# Main.net
KiCad netlist of a schematic drawn in Altium Designer
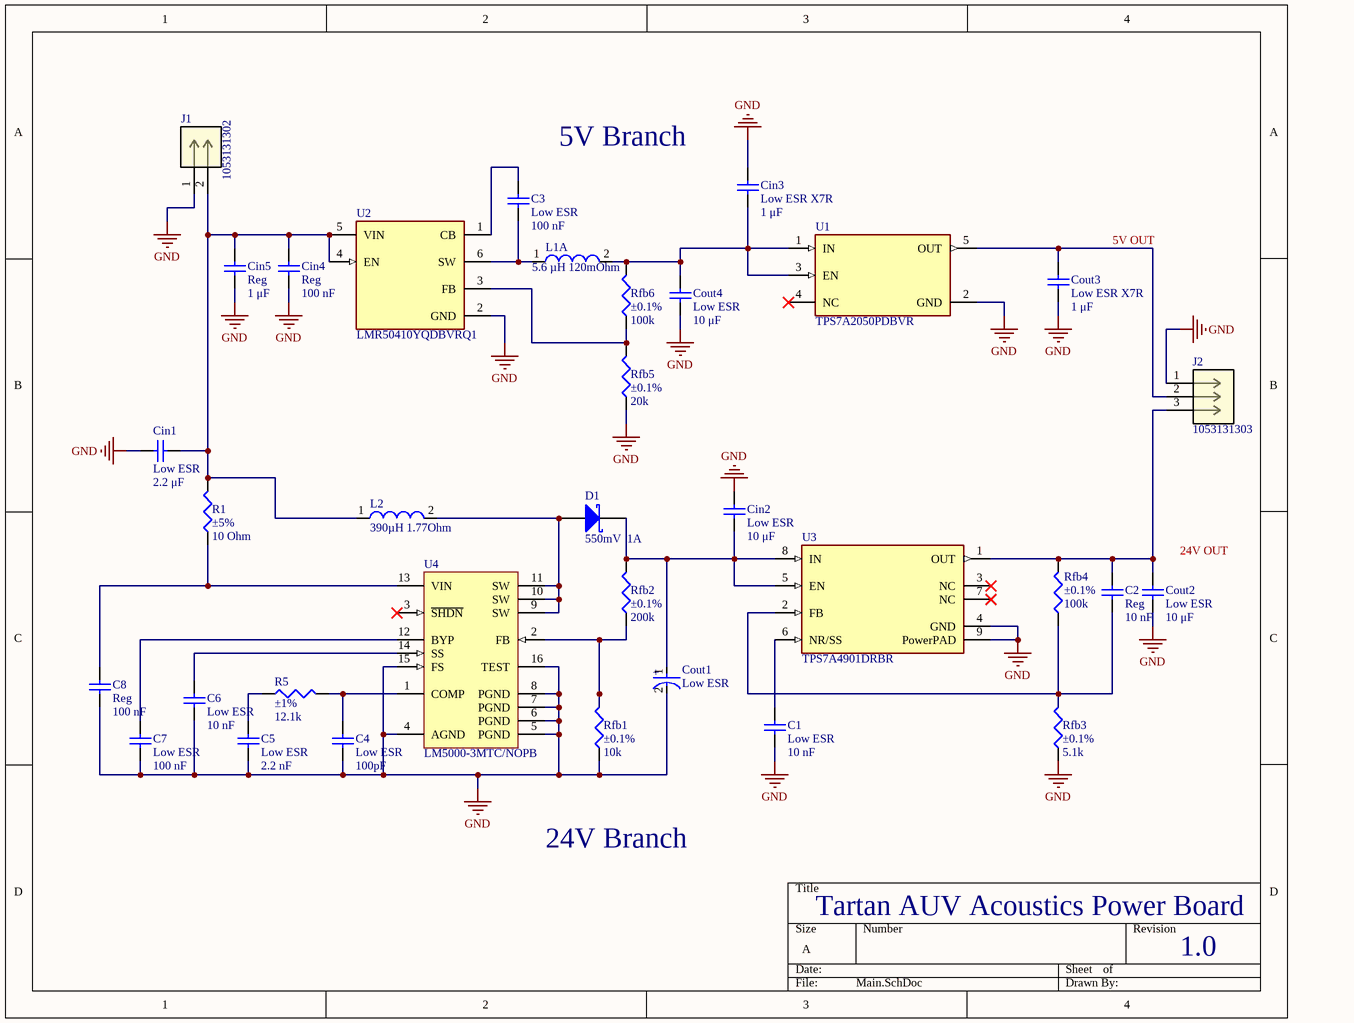
[diagram p0: Main.SchDoc]

(export (version "E")
  (design (tool "Eeschema 10.0.6"))
  (components
    (comp (ref "C1")
      (value "Low ESR")
      (footprint "C0805")
      (description "Capacitor")
      (fields (field (name "ALTIUM_VALUE") "10 nF") (field (name "PUBLISHER") "Altium Limited"))
      (libsource (lib "Miscellaneous Devices") (part "Cap"))
    )
    (comp (ref "C2")
      (value "Reg")
      (footprint "C0805")
      (description "Capacitor")
      (fields (field (name "ALTIUM_VALUE") "10 nF") (field (name "PUBLISHER") "Altium Limited"))
      (libsource (lib "Miscellaneous Devices") (part "Cap"))
    )
    (comp (ref "C3")
      (value "Low ESR")
      (footprint "C0805")
      (description "Capacitor")
      (fields (field (name "ALTIUM_VALUE") "100 nF") (field (name "PUBLISHER") "Altium Limited"))
      (libsource (lib "Miscellaneous Devices") (part "Cap"))
    )
    (comp (ref "C4")
      (value "Low ESR")
      (footprint "C0805")
      (description "Capacitor")
      (fields (field (name "ALTIUM_VALUE") "100pF") (field (name "PUBLISHER") "Altium Limited"))
      (libsource (lib "Miscellaneous Devices") (part "Cap"))
    )
    (comp (ref "C5")
      (value "Low ESR")
      (footprint "C0805")
      (description "Capacitor")
      (fields (field (name "ALTIUM_VALUE") "2.2 nF") (field (name "PUBLISHER") "Altium Limited"))
      (libsource (lib "Miscellaneous Devices") (part "Cap"))
    )
    (comp (ref "C6")
      (value "Low ESR")
      (footprint "C0805")
      (description "Capacitor")
      (fields (field (name "ALTIUM_VALUE") "10 nF") (field (name "PUBLISHER") "Altium Limited"))
      (libsource (lib "Miscellaneous Devices") (part "Cap"))
    )
    (comp (ref "C7")
      (value "Low ESR")
      (footprint "C0805")
      (description "Capacitor")
      (fields (field (name "ALTIUM_VALUE") "100 nF") (field (name "PUBLISHER") "Altium Limited"))
      (libsource (lib "Miscellaneous Devices") (part "Cap"))
    )
    (comp (ref "C8")
      (value "Reg")
      (footprint "C0805")
      (description "Capacitor")
      (fields (field (name "ALTIUM_VALUE") "100 nF") (field (name "PUBLISHER") "Altium Limited"))
      (libsource (lib "Miscellaneous Devices") (part "Cap"))
    )
    (comp (ref "Cin1")
      (value "Low ESR")
      (footprint "C0805")
      (description "Capacitor")
      (fields (field (name "ALTIUM_VALUE") "2.2 μF") (field (name "PUBLISHER") "Altium Limited"))
      (libsource (lib "Miscellaneous Devices") (part "Cap"))
    )
    (comp (ref "Cin2")
      (value "Low ESR")
      (footprint "C1210")
      (description "Capacitor")
      (fields (field (name "ALTIUM_VALUE") "10 μF") (field (name "PUBLISHER") "Altium Limited"))
      (libsource (lib "Miscellaneous Devices") (part "Cap"))
    )
    (comp (ref "Cin3")
      (value "Low ESR X7R")
      (footprint "C0805")
      (description "Capacitor")
      (fields (field (name "ALTIUM_VALUE") "1 μF") (field (name "PUBLISHER") "Altium Limited"))
      (libsource (lib "Miscellaneous Devices") (part "Cap"))
    )
    (comp (ref "Cin4")
      (value "Reg")
      (footprint "C0805")
      (description "Capacitor")
      (fields (field (name "ALTIUM_VALUE") "100 nF") (field (name "PUBLISHER") "Altium Limited"))
      (libsource (lib "Miscellaneous Devices") (part "Cap"))
    )
    (comp (ref "Cin5")
      (value "Reg")
      (footprint "C0805")
      (description "Capacitor")
      (fields (field (name "ALTIUM_VALUE") "1 μF") (field (name "PUBLISHER") "Altium Limited"))
      (libsource (lib "Miscellaneous Devices") (part "Cap"))
    )
    (comp (ref "Cout1")
      (value "Low ESR")
      (footprint "FP-EEH-D8-MFG")
      (description "Conductive Polymer Hybrid Aluminum Electrolytic Capacitors 68uF ±20% 35V RADIAL SMT 6.3x7.7mm")
      (fields (field (name "VOLTAGE") "35V") (field (name "TOLERANCE") "20%"))
      (libsource (lib "Altium Content Vault") (part "a00bbbee19879c290e62620ae7e47b1"))
    )
    (comp (ref "Cout2")
      (value "Low ESR")
      (footprint "C1210")
      (description "Capacitor")
      (fields (field (name "ALTIUM_VALUE") "10 μF") (field (name "PUBLISHER") "Altium Limited"))
      (libsource (lib "Miscellaneous Devices") (part "Cap"))
    )
    (comp (ref "Cout3")
      (value "Low ESR X7R")
      (footprint "C0805")
      (description "Capacitor")
      (fields (field (name "ALTIUM_VALUE") "1 μF") (field (name "PUBLISHER") "Altium Limited"))
      (libsource (lib "Miscellaneous Devices") (part "Cap"))
    )
    (comp (ref "Cout4")
      (value "Low ESR")
      (footprint "C1210")
      (description "Capacitor")
      (fields (field (name "ALTIUM_VALUE") "10 μF") (field (name "PUBLISHER") "Altium Limited"))
      (libsource (lib "Miscellaneous Devices") (part "Cap"))
    )
    (comp (ref "D1")
      (value "550mV  1A")
      (footprint "SMB")
      (description "Schottky Diode")
      (fields (field (name "PUBLISHER") "Altium Limited"))
      (libsource (lib "Miscellaneous Devices") (part "D Schottky"))
    )
    (comp (ref "J1")
      (value "1053131302")
      (footprint "CON_1053131302")
      (description "No Description Available")
      (fields (field (name "COPYRIGHT") "Copyright (C) 2022 Ultra Librarian. All rights reserved."))
      (libsource (lib "1053131302") (part "1053131302"))
    )
    (comp (ref "J2")
      (value "1053131303")
      (footprint "CON_1053131303")
      (description "No Description Available")
      (fields (field (name "COPYRIGHT") "Copyright (C) 2022 Ultra Librarian. All rights reserved."))
      (libsource (lib "1053131303") (part "1053131303"))
    )
    (comp (ref "L1")
      (value "5.6 µH 120mOhm")
      (footprint "WE-TPC-8012")
      (description "SMD Shielded Tiny Power Inductor WE-TPC, L = 5.60 µH")
      (libsource (lib "Altium Content Vault") (part "PAS-IND-INDUCTOR-4L"))
    )
    (comp (ref "L2")
      (value "390µH 1.77Ohm")
      (footprint "WE-PD2-L")
      (description "SMD Power Inductor WE-PD2, L = 390 µH")
      (libsource (lib "Altium Content Vault") (part "PAS-IND-INDUCTOR-2"))
    )
    (comp (ref "R1")
      (value "±5%")
      (footprint "J1-0603")
      (description "Resistor")
      (fields (field (name "ALTIUM_VALUE") "10 Ohm") (field (name "PUBLISHER") "Altium Limited"))
      (libsource (lib "Miscellaneous Devices") (part "Res3"))
    )
    (comp (ref "R5")
      (value "±1%")
      (footprint "J1-0603")
      (description "Resistor")
      (fields (field (name "ALTIUM_VALUE") "12.1k") (field (name "PUBLISHER") "Altium Limited"))
      (libsource (lib "Miscellaneous Devices") (part "Res3"))
    )
    (comp (ref "Rfb1")
      (value "±0.1%")
      (footprint "J1-0603")
      (description "Resistor")
      (fields (field (name "ALTIUM_VALUE") "10k") (field (name "PUBLISHER") "Altium Limited"))
      (libsource (lib "Miscellaneous Devices") (part "Res3"))
    )
    (comp (ref "Rfb2")
      (value "±0.1%")
      (footprint "J1-0603")
      (description "Resistor")
      (fields (field (name "ALTIUM_VALUE") "200k") (field (name "PUBLISHER") "Altium Limited"))
      (libsource (lib "Miscellaneous Devices") (part "Res3"))
    )
    (comp (ref "Rfb3")
      (value "±0.1%")
      (footprint "J1-0603")
      (description "Resistor")
      (fields (field (name "ALTIUM_VALUE") "5.1k") (field (name "PUBLISHER") "Altium Limited"))
      (libsource (lib "Miscellaneous Devices") (part "Res3"))
    )
    (comp (ref "Rfb4")
      (value "±0.1%")
      (footprint "J1-0603")
      (description "Resistor")
      (fields (field (name "ALTIUM_VALUE") "100k") (field (name "PUBLISHER") "Altium Limited"))
      (libsource (lib "Miscellaneous Devices") (part "Res3"))
    )
    (comp (ref "Rfb5")
      (value "±0.1%")
      (footprint "J1-0603")
      (description "Resistor")
      (fields (field (name "ALTIUM_VALUE") "20k") (field (name "PUBLISHER") "Altium Limited"))
      (libsource (lib "Miscellaneous Devices") (part "Res3"))
    )
    (comp (ref "Rfb6")
      (value "±0.1%")
      (footprint "J1-0603")
      (description "Resistor")
      (fields (field (name "ALTIUM_VALUE") "100k") (field (name "PUBLISHER") "Altium Limited"))
      (libsource (lib "Miscellaneous Devices") (part "Res3"))
    )
    (comp (ref "U1")
      (value "TPS7A2050PDBVR")
      (footprint "FP-DBV0005A-IPC_B")
      (libsource (lib "Altium Content Vault") (part "016a98dcc07c0606c38eea974f4970a"))
    )
    (comp (ref "U2")
      (value "LMR50410YQDBVRQ1")
      (footprint "FP-DBV0006A-MFG")
      (description "NIXON PLUS-LMR50410YQDBVRQ1")
      (libsource (lib "Altium Content Vault") (part "dd20875c80c3702360114ef84ecc10b"))
    )
    (comp (ref "U3")
      (value "TPS7A4901DRBR")
      (footprint "FP-DRB0008A-MFG")
      (description "None")
      (libsource (lib "Altium Content Vault") (part "ef16affa275921b576f8415521af00b"))
    )
    (comp (ref "U4")
      (value "LM5000-3MTC/NOPB")
      (footprint "PW0016A_L")
      (description "High Voltage Switch Mode Regulator, 16-pin TSSOP, Pb-Free")
      (fields (field (name "MANUFACTURER") "Texas Instruments"))
      (libsource (lib "Altium Content Vault") (part "PM-SMPS-LM5000-16"))
    )
  )
  (nets
    (net (code "1") (name "GND") (class "Default")
      (node (ref "C1") (pin "1") (pinfunction "1_1") (pintype "passive"))
      (node (ref "C4") (pin "1") (pinfunction "1_1") (pintype "passive"))
      (node (ref "C5") (pin "1") (pinfunction "1_1") (pintype "passive"))
      (node (ref "C6") (pin "1") (pinfunction "1_1") (pintype "passive"))
      (node (ref "C7") (pin "1") (pinfunction "1_1") (pintype "passive"))
      (node (ref "C8") (pin "1") (pinfunction "1_1") (pintype "passive"))
      (node (ref "Cin1") (pin "1") (pinfunction "1_1") (pintype "passive"))
      (node (ref "Cin2") (pin "2") (pinfunction "2_2") (pintype "passive"))
      (node (ref "Cin3") (pin "2") (pinfunction "2_2") (pintype "passive"))
      (node (ref "Cin4") (pin "1") (pinfunction "1_1") (pintype "passive"))
      (node (ref "Cin5") (pin "1") (pinfunction "1_1") (pintype "passive"))
      (node (ref "Cout1") (pin "2") (pinfunction "A_2") (pintype "passive"))
      (node (ref "Cout2") (pin "1") (pinfunction "1_1") (pintype "passive"))
      (node (ref "Cout3") (pin "1") (pinfunction "1_1") (pintype "passive"))
      (node (ref "Cout4") (pin "1") (pinfunction "1_1") (pintype "passive"))
      (node (ref "J1") (pin "1") (pinfunction "1_1") (pintype "passive"))
      (node (ref "J2") (pin "1") (pinfunction "1_1") (pintype "passive"))
      (node (ref "Rfb1") (pin "1") (pinfunction "1_1") (pintype "passive"))
      (node (ref "Rfb3") (pin "1") (pinfunction "1_1") (pintype "passive"))
      (node (ref "Rfb5") (pin "1") (pinfunction "1_1") (pintype "passive"))
      (node (ref "U1") (pin "2") (pinfunction "GND_2") (pintype "power_in"))
      (node (ref "U2") (pin "2") (pinfunction "GND_2") (pintype "power_in"))
      (node (ref "U3") (pin "4") (pinfunction "GND_4") (pintype "power_in"))
      (node (ref "U3") (pin "9") (pinfunction "PowerPAD_9") (pintype "power_in"))
      (node (ref "U4") (pin "15") (pinfunction "FS_15") (pintype "input"))
      (node (ref "U4") (pin "16") (pinfunction "TEST_16") (pintype "passive"))
      (node (ref "U4") (pin "4") (pinfunction "AGND_4") (pintype "power_in"))
      (node (ref "U4") (pin "5") (pinfunction "PGND_5") (pintype "power_in"))
      (node (ref "U4") (pin "6") (pinfunction "PGND_6") (pintype "power_in"))
      (node (ref "U4") (pin "7") (pinfunction "PGND_7") (pintype "power_in"))
      (node (ref "U4") (pin "8") (pinfunction "PGND_8") (pintype "power_in"))
    )
    (net (code "2") (name "Net-(C5-Pad2)") (class "Default")
      (node (ref "C5") (pin "2") (pinfunction "2_2") (pintype "passive"))
      (node (ref "R5") (pin "1") (pinfunction "1_1") (pintype "passive"))
    )
    (net (code "3") (name "Net-(Cout1-C)") (class "Default")
      (node (ref "Cin2") (pin "1") (pinfunction "1_1") (pintype "passive"))
      (node (ref "Cout1") (pin "1") (pinfunction "C_1") (pintype "passive"))
      (node (ref "D1") (pin "2") (pinfunction "K_2") (pintype "passive"))
      (node (ref "Rfb2") (pin "2") (pinfunction "2_2") (pintype "passive"))
      (node (ref "U3") (pin "5") (pinfunction "EN_5") (pintype "input"))
      (node (ref "U3") (pin "8") (pinfunction "IN_8") (pintype "input"))
    )
    (net (code "4") (name "Net-(D1-A)") (class "Default")
      (node (ref "D1") (pin "1") (pinfunction "A_1") (pintype "passive"))
      (node (ref "L2") (pin "2") (pinfunction "2_2") (pintype "passive"))
      (node (ref "U4") (pin "10") (pinfunction "SW_10") (pintype "power_in"))
      (node (ref "U4") (pin "11") (pinfunction "SW_11") (pintype "power_in"))
      (node (ref "U4") (pin "9") (pinfunction "SW_9") (pintype "power_in"))
    )
    (net (code "5") (name "Net-(U1-EN)") (class "Default")
      (node (ref "Cin3") (pin "1") (pinfunction "1_1") (pintype "passive"))
      (node (ref "Cout4") (pin "2") (pinfunction "2_2") (pintype "passive"))
      (node (ref "L1") (pin "2") (pinfunction "2_2") (pintype "passive"))
      (node (ref "Rfb6") (pin "2") (pinfunction "2_2") (pintype "passive"))
      (node (ref "U1") (pin "1") (pinfunction "IN_1") (pintype "input"))
      (node (ref "U1") (pin "3") (pinfunction "EN_3") (pintype "input"))
    )
    (net (code "6") (name "Net-(U1-OUT)") (class "Default")
      (node (ref "Cout3") (pin "2") (pinfunction "2_2") (pintype "passive"))
      (node (ref "J2") (pin "2") (pinfunction "2_2") (pintype "passive"))
      (node (ref "U1") (pin "5") (pinfunction "OUT_5") (pintype "output"))
    )
    (net (code "7") (name "Net-(U2-CB)") (class "Default")
      (node (ref "C3") (pin "2") (pinfunction "2_2") (pintype "passive"))
      (node (ref "U2") (pin "1") (pinfunction "CB_1") (pintype "passive"))
    )
    (net (code "8") (name "Net-(U2-EN)") (class "Default")
      (node (ref "Cin1") (pin "2") (pinfunction "2_2") (pintype "passive"))
      (node (ref "Cin4") (pin "2") (pinfunction "2_2") (pintype "passive"))
      (node (ref "Cin5") (pin "2") (pinfunction "2_2") (pintype "passive"))
      (node (ref "J1") (pin "2") (pinfunction "2_2") (pintype "passive"))
      (node (ref "L2") (pin "1") (pinfunction "1_1") (pintype "passive"))
      (node (ref "R1") (pin "2") (pinfunction "2_2") (pintype "passive"))
      (node (ref "U2") (pin "4") (pinfunction "EN_4") (pintype "input"))
      (node (ref "U2") (pin "5") (pinfunction "VIN_5") (pintype "power_in"))
    )
    (net (code "9") (name "Net-(U2-FB)") (class "Default")
      (node (ref "Rfb5") (pin "2") (pinfunction "2_2") (pintype "passive"))
      (node (ref "Rfb6") (pin "1") (pinfunction "1_1") (pintype "passive"))
      (node (ref "U2") (pin "3") (pinfunction "FB_3") (pintype "passive"))
    )
    (net (code "10") (name "Net-(U2-SW)") (class "Default")
      (node (ref "C3") (pin "1") (pinfunction "1_1") (pintype "passive"))
      (node (ref "L1") (pin "1") (pinfunction "1_1") (pintype "passive"))
      (node (ref "U2") (pin "6") (pinfunction "SW_6") (pintype "power_in"))
    )
    (net (code "11") (name "Net-(U3-FB)") (class "Default")
      (node (ref "C2") (pin "1") (pinfunction "1_1") (pintype "passive"))
      (node (ref "Rfb3") (pin "2") (pinfunction "2_2") (pintype "passive"))
      (node (ref "Rfb4") (pin "1") (pinfunction "1_1") (pintype "passive"))
      (node (ref "U3") (pin "2") (pinfunction "FB_2") (pintype "input"))
    )
    (net (code "12") (name "Net-(U3-NR{slash}SS)") (class "Default")
      (node (ref "C1") (pin "2") (pinfunction "2_2") (pintype "passive"))
      (node (ref "U3") (pin "6") (pinfunction "NR/SS_6") (pintype "input"))
    )
    (net (code "13") (name "Net-(U3-OUT)") (class "Default")
      (node (ref "C2") (pin "2") (pinfunction "2_2") (pintype "passive"))
      (node (ref "Cout2") (pin "2") (pinfunction "2_2") (pintype "passive"))
      (node (ref "J2") (pin "3") (pinfunction "3_3") (pintype "passive"))
      (node (ref "Rfb4") (pin "2") (pinfunction "2_2") (pintype "passive"))
      (node (ref "U3") (pin "1") (pinfunction "OUT_1") (pintype "output"))
    )
    (net (code "14") (name "Net-(U4-BYP)") (class "Default")
      (node (ref "C7") (pin "2") (pinfunction "2_2") (pintype "passive"))
      (node (ref "U4") (pin "12") (pinfunction "BYP_12") (pintype "passive"))
    )
    (net (code "15") (name "Net-(U4-COMP)") (class "Default")
      (node (ref "C4") (pin "2") (pinfunction "2_2") (pintype "passive"))
      (node (ref "R5") (pin "2") (pinfunction "2_2") (pintype "passive"))
      (node (ref "U4") (pin "1") (pinfunction "COMP_1") (pintype "passive"))
    )
    (net (code "16") (name "Net-(U4-FB)") (class "Default")
      (node (ref "Rfb1") (pin "2") (pinfunction "2_2") (pintype "passive"))
      (node (ref "Rfb2") (pin "1") (pinfunction "1_1") (pintype "passive"))
      (node (ref "U4") (pin "2") (pinfunction "FB_2") (pintype "input"))
    )
    (net (code "17") (name "Net-(U4-SS)") (class "Default")
      (node (ref "C6") (pin "2") (pinfunction "2_2") (pintype "passive"))
      (node (ref "U4") (pin "14") (pinfunction "SS_14") (pintype "input"))
    )
    (net (code "18") (name "Net-(U4-VIN)") (class "Default")
      (node (ref "C8") (pin "2") (pinfunction "2_2") (pintype "passive"))
      (node (ref "R1") (pin "1") (pinfunction "1_1") (pintype "passive"))
      (node (ref "U4") (pin "13") (pinfunction "VIN_13") (pintype "power_in"))
    )
    (net (code "19") (name "unconnected-(U1-NC-Pad4)") (class "Default")
      (node (ref "U1") (pin "4") (pinfunction "NC_4") (pintype "passive+no_connect"))
    )
    (net (code "20") (name "unconnected-(U3-NC-Pad3)") (class "Default")
      (node (ref "U3") (pin "3") (pinfunction "NC_3") (pintype "passive+no_connect"))
    )
    (net (code "21") (name "unconnected-(U3-NC-Pad7)") (class "Default")
      (node (ref "U3") (pin "7") (pinfunction "NC_7") (pintype "passive+no_connect"))
    )
    (net (code "22") (name "unconnected-(U4-~{SHDN}-Pad3)") (class "Default")
      (node (ref "U4") (pin "3") (pinfunction "~{SHDN}_3") (pintype "input+no_connect"))
    )
  )
)
